# contactorcontactor.net
KiCad netlist of a schematic drawn in EAGLE
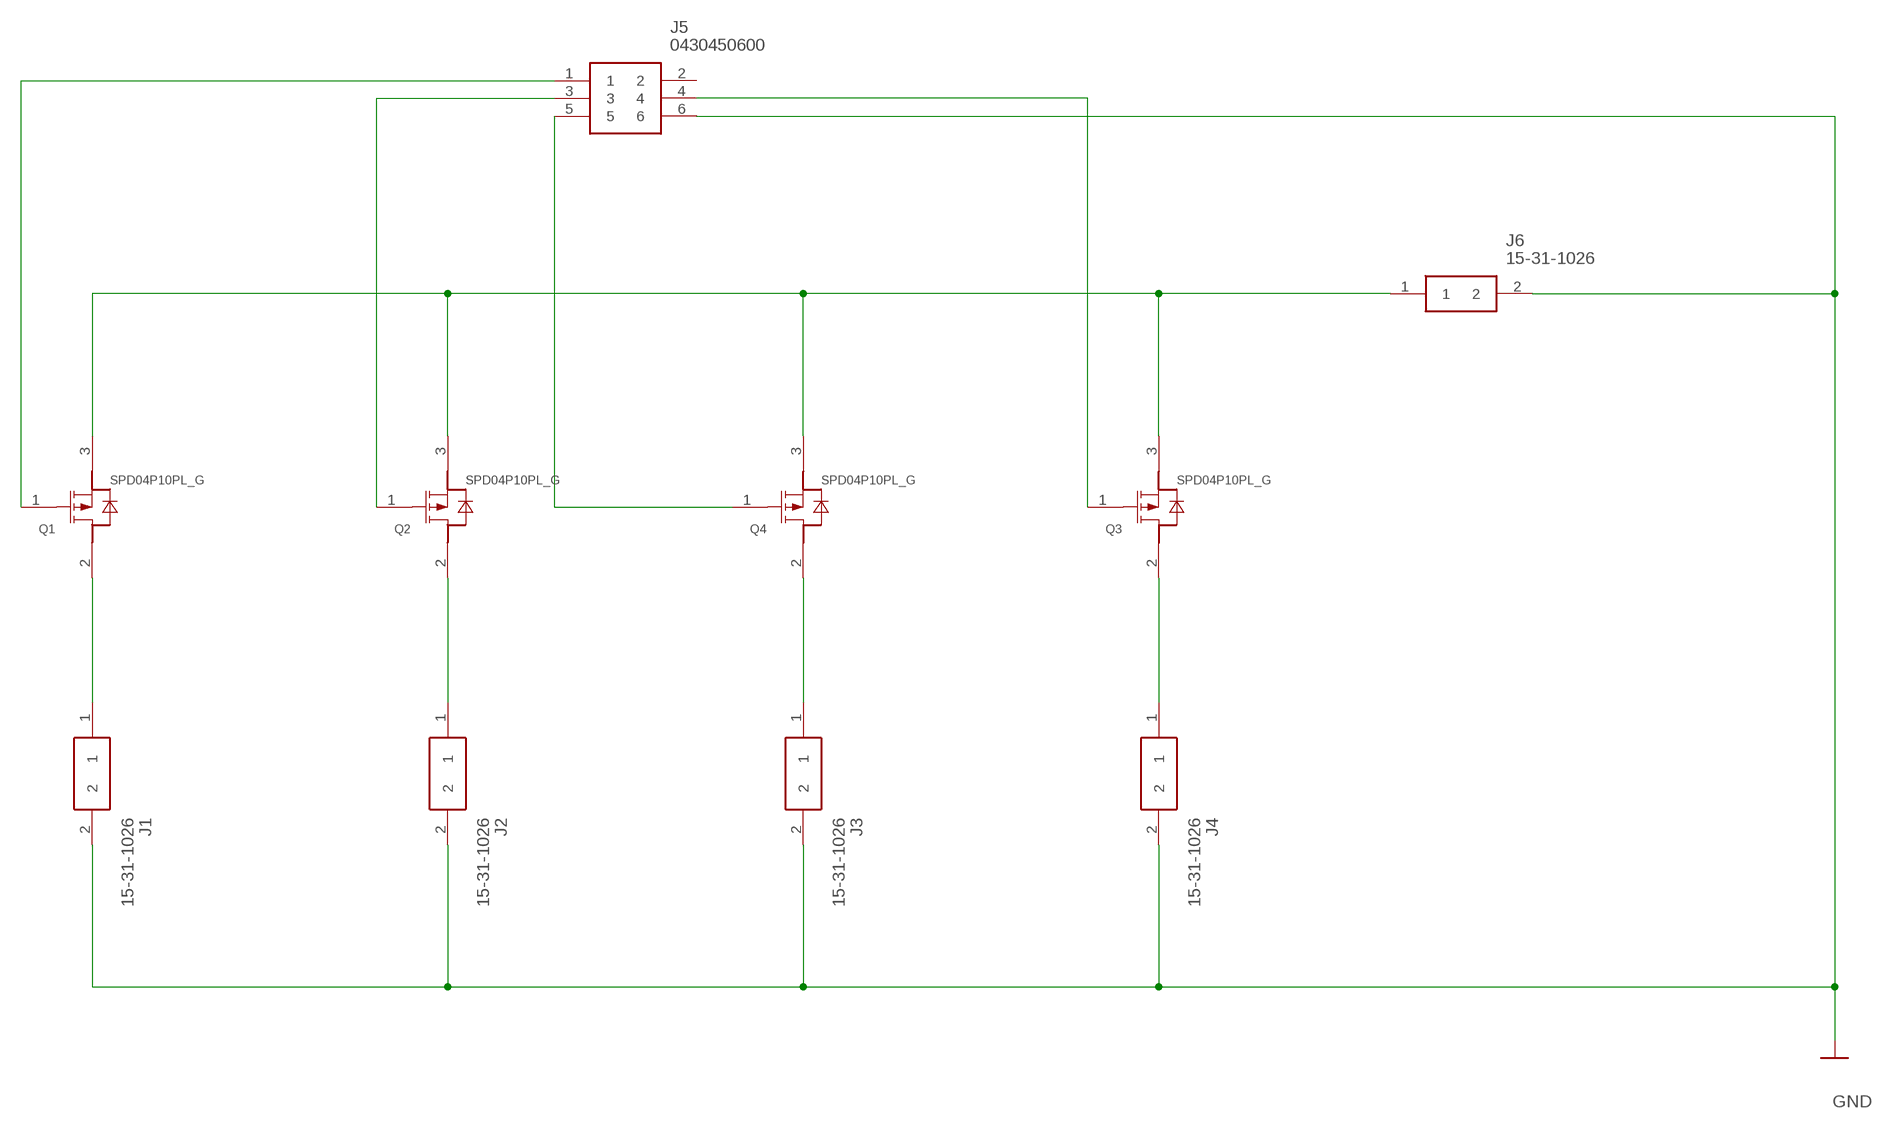
[diagram p0: schematic, sheet 1]

(export (version "E")
  (design (tool "Eeschema 10.0.6"))
  (components
    (comp (ref "J1")
      (value "15-31-1026")
      (footprint "eagle-import:15311026")
      (fields (field (name "MOUSER_PART_NUMBER") "538-15-31-1026") (field (name "RS_PART_NUMBER") "6700289"))
      (libsource (lib "eagle-import") (part "15-31-1026"))
    )
    (comp (ref "J2")
      (value "15-31-1026")
      (footprint "eagle-import:15311026")
      (fields (field (name "MOUSER_PART_NUMBER") "538-15-31-1026") (field (name "RS_PART_NUMBER") "6700289"))
      (libsource (lib "eagle-import") (part "15-31-1026"))
    )
    (comp (ref "J3")
      (value "15-31-1026")
      (footprint "eagle-import:15311026")
      (fields (field (name "MOUSER_PART_NUMBER") "538-15-31-1026") (field (name "RS_PART_NUMBER") "6700289"))
      (libsource (lib "eagle-import") (part "15-31-1026"))
    )
    (comp (ref "J4")
      (value "15-31-1026")
      (footprint "eagle-import:15311026")
      (fields (field (name "MOUSER_PART_NUMBER") "538-15-31-1026") (field (name "RS_PART_NUMBER") "6700289"))
      (libsource (lib "eagle-import") (part "15-31-1026"))
    )
    (comp (ref "J5")
      (value "0430450600")
      (footprint "eagle-import:0430450601")
      (libsource (lib "eagle-import") (part "0430450600"))
    )
    (comp (ref "J6")
      (value "15-31-1026")
      (footprint "eagle-import:15311026")
      (fields (field (name "MOUSER_PART_NUMBER") "538-15-31-1026") (field (name "RS_PART_NUMBER") "6700289"))
      (libsource (lib "eagle-import") (part "15-31-1026"))
    )
    (comp (ref "Q1")
      (value "SPD04P10PL_G")
      (footprint "eagle-import:TO229P994X241-3N")
      (libsource (lib "eagle-import") (part "SPD04P10PL_G"))
    )
    (comp (ref "Q2")
      (value "SPD04P10PL_G")
      (footprint "eagle-import:TO229P994X241-3N")
      (libsource (lib "eagle-import") (part "SPD04P10PL_G"))
    )
    (comp (ref "Q3")
      (value "SPD04P10PL_G")
      (footprint "eagle-import:TO229P994X241-3N")
      (libsource (lib "eagle-import") (part "SPD04P10PL_G"))
    )
    (comp (ref "Q4")
      (value "SPD04P10PL_G")
      (footprint "eagle-import:TO229P994X241-3N")
      (libsource (lib "eagle-import") (part "SPD04P10PL_G"))
    )
  )
  (nets
    (net (code "1") (name "GND") (class "Default")
      (node (ref "J1") (pin "2") (pinfunction "2_2") (pintype "bidirectional"))
      (node (ref "J2") (pin "2") (pinfunction "2_2") (pintype "bidirectional"))
      (node (ref "J3") (pin "2") (pinfunction "2_2") (pintype "bidirectional"))
      (node (ref "J4") (pin "2") (pinfunction "2_2") (pintype "bidirectional"))
      (node (ref "J5") (pin "6") (pinfunction "6_6") (pintype "bidirectional"))
      (node (ref "J6") (pin "2") (pinfunction "2_2") (pintype "bidirectional"))
    )
    (net (code "2") (name "Net-(J1-Pad1)") (class "Default")
      (node (ref "J1") (pin "1") (pinfunction "1_1") (pintype "bidirectional"))
      (node (ref "Q1") (pin "2") (pinfunction "2_2") (pintype "bidirectional"))
    )
    (net (code "3") (name "Net-(J2-Pad1)") (class "Default")
      (node (ref "J2") (pin "1") (pinfunction "1_1") (pintype "bidirectional"))
      (node (ref "Q2") (pin "2") (pinfunction "2_2") (pintype "bidirectional"))
    )
    (net (code "4") (name "Net-(J3-Pad1)") (class "Default")
      (node (ref "J3") (pin "1") (pinfunction "1_1") (pintype "bidirectional"))
      (node (ref "Q4") (pin "2") (pinfunction "2_2") (pintype "bidirectional"))
    )
    (net (code "5") (name "Net-(J4-Pad1)") (class "Default")
      (node (ref "J4") (pin "1") (pinfunction "1_1") (pintype "bidirectional"))
      (node (ref "Q3") (pin "2") (pinfunction "2_2") (pintype "bidirectional"))
    )
    (net (code "6") (name "Net-(J5-Pad1)") (class "Default")
      (node (ref "J5") (pin "1") (pinfunction "1_1") (pintype "bidirectional"))
      (node (ref "Q1") (pin "1") (pinfunction "1_1") (pintype "passive"))
    )
    (net (code "7") (name "Net-(J5-Pad3)") (class "Default")
      (node (ref "J5") (pin "3") (pinfunction "3_3") (pintype "bidirectional"))
      (node (ref "Q2") (pin "1") (pinfunction "1_1") (pintype "passive"))
    )
    (net (code "8") (name "Net-(J5-Pad4)") (class "Default")
      (node (ref "J5") (pin "4") (pinfunction "4_4") (pintype "bidirectional"))
      (node (ref "Q3") (pin "1") (pinfunction "1_1") (pintype "passive"))
    )
    (net (code "9") (name "Net-(J5-Pad5)") (class "Default")
      (node (ref "J5") (pin "5") (pinfunction "5_5") (pintype "bidirectional"))
      (node (ref "Q4") (pin "1") (pinfunction "1_1") (pintype "passive"))
    )
    (net (code "10") (name "Net-(J6-Pad1)") (class "Default")
      (node (ref "J6") (pin "1") (pinfunction "1_1") (pintype "bidirectional"))
      (node (ref "Q1") (pin "3") (pinfunction "3_3") (pintype "passive"))
      (node (ref "Q2") (pin "3") (pinfunction "3_3") (pintype "passive"))
      (node (ref "Q3") (pin "3") (pinfunction "3_3") (pintype "passive"))
      (node (ref "Q4") (pin "3") (pinfunction "3_3") (pintype "passive"))
    )
    (net (code "11") (name "unconnected-(J5-Pad2)") (class "Default")
      (node (ref "J5") (pin "2") (pinfunction "2_2") (pintype "bidirectional"))
    )
  )
)
